# mgmt.net
KiCad netlist of a schematic drawn in Altium Designer
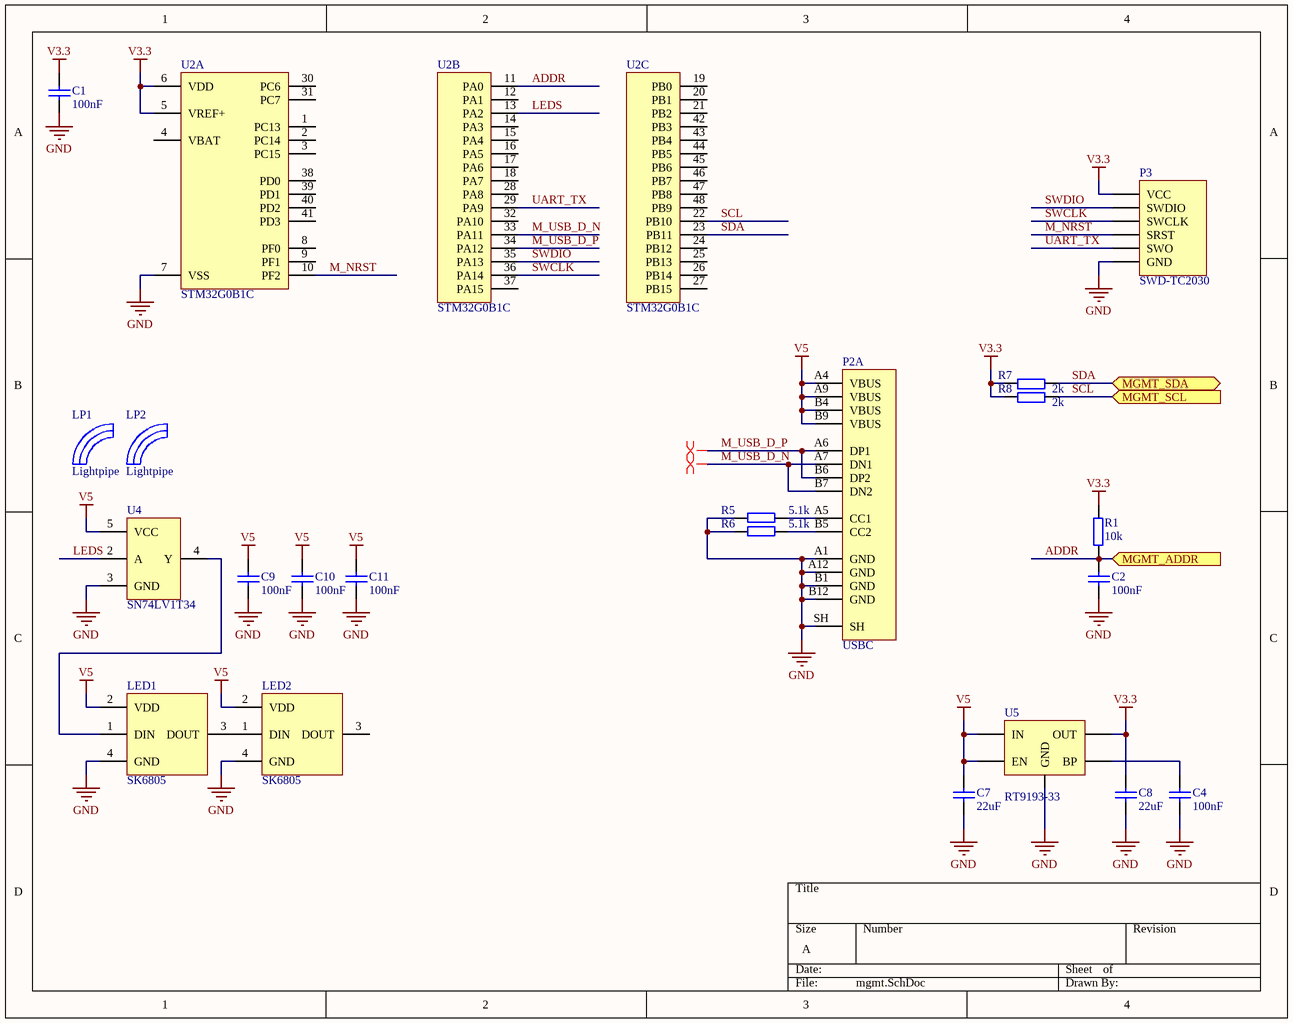
[diagram p0: mgmt.SchDoc]

(export (version "E")
  (design (tool "Eeschema 10.0.6"))
  (components
    (comp (ref "C1") (value "100nF") (footprint "0402") (libsource (lib "misc") (part "Capacitor")))
    (comp (ref "C2") (value "100nF") (footprint "0402") (libsource (lib "misc") (part "Capacitor")))
    (comp (ref "C4") (value "100nF") (footprint "0402") (libsource (lib "misc") (part "Capacitor")))
    (comp (ref "C7") (value "22uF") (footprint "0805") (libsource (lib "misc") (part "Capacitor")))
    (comp (ref "C8") (value "22uF") (footprint "0805") (libsource (lib "misc") (part "Capacitor")))
    (comp (ref "C9") (value "100nF") (footprint "0402") (libsource (lib "misc") (part "Capacitor")))
    (comp (ref "C10") (value "100nF") (footprint "0402") (libsource (lib "misc") (part "Capacitor")))
    (comp (ref "C11") (value "100nF") (footprint "0402") (libsource (lib "misc") (part "Capacitor")))
    (comp (ref "LED1") (value "SK6805") (footprint "EC15") (libsource (lib "misc") (part "SK6805")))
    (comp (ref "LED2") (value "SK6805") (footprint "EC15") (libsource (lib "misc") (part "SK6805")))
    (comp (ref "LP1")
      (value "Lightpipe")
      (footprint "SLP3-150-100-F")
      (libsource (lib "misc") (part "Lightpipe"))
    )
    (comp (ref "LP2")
      (value "Lightpipe")
      (footprint "SLP3-150-100-F")
      (libsource (lib "misc") (part "Lightpipe"))
    )
    (comp (ref "P2") (value "USBC") (footprint "U262-161N-4BVC11") (libsource (lib "misc") (part "USBC")))
    (comp (ref "P3")
      (value "SWD-TC2030")
      (footprint "TC2030-NL")
      (libsource (lib "misc") (part "SWD-TC2030"))
    )
    (comp (ref "R1") (value "10k") (footprint "0402") (libsource (lib "misc") (part "Resistor")))
    (comp (ref "R5") (value "5.1k") (footprint "0402") (libsource (lib "misc") (part "Resistor")))
    (comp (ref "R6") (value "5.1k") (footprint "0402") (libsource (lib "misc") (part "Resistor")))
    (comp (ref "R7") (value "2k") (footprint "0402") (libsource (lib "misc") (part "Resistor")))
    (comp (ref "R8") (value "2k") (footprint "0402") (libsource (lib "misc") (part "Resistor")))
    (comp (ref "U2") (value "STM32G0B1C") (footprint "QFP48") (libsource (lib "misc") (part "STM32G0B1C")))
    (comp (ref "U4")
      (value "SN74LV1T34")
      (footprint "SOT23-5")
      (description "Single Power Supply Single Buffer GATE CMOS Logic Level Shifter")
      (libsource (lib "misc") (part "SN74LV1T34"))
    )
    (comp (ref "U5") (value "RT9193-33") (footprint "SOT23-5") (libsource (lib "misc") (part "VREG_EN_BP")))
  )
  (nets
    (net (code "1") (name "/ADDR") (class "Default")
      (node (ref "C2") (pin "2") (pinfunction "2_2") (pintype "passive"))
      (node (ref "R1") (pin "1") (pinfunction "1_1") (pintype "passive"))
      (node (ref "U2") (pin "11") (pinfunction "PA0_11") (pintype "passive"))
    )
    (net (code "2") (name "/LEDS") (class "Default")
      (node (ref "U2") (pin "13") (pinfunction "PA2_13") (pintype "passive"))
      (node (ref "U4") (pin "2") (pinfunction "A_2") (pintype "passive"))
    )
    (net (code "3") (name "/M_NRST") (class "Default")
      (node (ref "P3") (pin "SRST") (pinfunction "SRST_SRST") (pintype "passive"))
      (node (ref "U2") (pin "10") (pinfunction "PF2_10") (pintype "passive"))
    )
    (net (code "4") (name "/M_USB_D_N") (class "Default")
      (node (ref "P2") (pin "A7") (pinfunction "DN1_A7") (pintype "passive"))
      (node (ref "P2") (pin "B7") (pinfunction "DN2_B7") (pintype "passive"))
      (node (ref "U2") (pin "33") (pinfunction "PA11_33") (pintype "passive"))
    )
    (net (code "5") (name "/M_USB_D_P") (class "Default")
      (node (ref "P2") (pin "A6") (pinfunction "DP1_A6") (pintype "passive"))
      (node (ref "P2") (pin "B6") (pinfunction "DP2_B6") (pintype "passive"))
      (node (ref "U2") (pin "34") (pinfunction "PA12_34") (pintype "passive"))
    )
    (net (code "6") (name "/SCL") (class "Default")
      (node (ref "R8") (pin "1") (pinfunction "1_1") (pintype "passive"))
      (node (ref "U2") (pin "22") (pinfunction "PB10_22") (pintype "passive"))
    )
    (net (code "7") (name "/SDA") (class "Default")
      (node (ref "R7") (pin "1") (pinfunction "1_1") (pintype "passive"))
      (node (ref "U2") (pin "23") (pinfunction "PB11_23") (pintype "passive"))
    )
    (net (code "8") (name "/SWCLK") (class "Default")
      (node (ref "P3") (pin "SWCLK") (pinfunction "SWCLK_SWCLK") (pintype "passive"))
      (node (ref "U2") (pin "36") (pinfunction "PA14_36") (pintype "passive"))
    )
    (net (code "9") (name "/SWDIO") (class "Default")
      (node (ref "P3") (pin "SWDIO") (pinfunction "SWDIO_SWDIO") (pintype "passive"))
      (node (ref "U2") (pin "35") (pinfunction "PA13_35") (pintype "passive"))
    )
    (net (code "10") (name "/UART_TX") (class "Default")
      (node (ref "P3") (pin "SWO") (pinfunction "SWO_SWO") (pintype "passive"))
      (node (ref "U2") (pin "29") (pinfunction "PA9_29") (pintype "passive"))
    )
    (net (code "11") (name "GND") (class "Default")
      (node (ref "C1") (pin "1") (pinfunction "1_1") (pintype "passive"))
      (node (ref "C10") (pin "1") (pinfunction "1_1") (pintype "passive"))
      (node (ref "C11") (pin "1") (pinfunction "1_1") (pintype "passive"))
      (node (ref "C2") (pin "1") (pinfunction "1_1") (pintype "passive"))
      (node (ref "C4") (pin "1") (pinfunction "1_1") (pintype "passive"))
      (node (ref "C7") (pin "1") (pinfunction "1_1") (pintype "passive"))
      (node (ref "C8") (pin "1") (pinfunction "1_1") (pintype "passive"))
      (node (ref "C9") (pin "1") (pinfunction "1_1") (pintype "passive"))
      (node (ref "LED1") (pin "4") (pinfunction "GND_4") (pintype "passive"))
      (node (ref "LED2") (pin "4") (pinfunction "GND_4") (pintype "passive"))
      (node (ref "P2") (pin "A1") (pinfunction "GND_A1") (pintype "passive"))
      (node (ref "P2") (pin "A12") (pinfunction "GND_A12") (pintype "passive"))
      (node (ref "P2") (pin "B1") (pinfunction "GND_B1") (pintype "passive"))
      (node (ref "P2") (pin "B12") (pinfunction "GND_B12") (pintype "passive"))
      (node (ref "P2") (pin "SH") (pinfunction "SH_SH") (pintype "passive"))
      (node (ref "P3") (pin "GND") (pinfunction "GND_GND") (pintype "passive"))
      (node (ref "R5") (pin "1") (pinfunction "1_1") (pintype "passive"))
      (node (ref "R6") (pin "1") (pinfunction "1_1") (pintype "passive"))
      (node (ref "U2") (pin "7") (pinfunction "VSS_7") (pintype "passive"))
      (node (ref "U4") (pin "3") (pinfunction "GND_3") (pintype "passive"))
      (node (ref "U5") (pin "GND") (pinfunction "GND_GND") (pintype "passive"))
    )
    (net (code "12") (name "Net-(C4-Pad2)") (class "Default")
      (node (ref "C4") (pin "2") (pinfunction "2_2") (pintype "passive"))
      (node (ref "U5") (pin "BP") (pinfunction "BP_BP") (pintype "passive"))
    )
    (net (code "13") (name "Net-(LED1-DIN)") (class "Default")
      (node (ref "LED1") (pin "1") (pinfunction "DIN_1") (pintype "passive"))
      (node (ref "U4") (pin "4") (pinfunction "Y_4") (pintype "passive"))
    )
    (net (code "14") (name "Net-(LED1-DOUT)") (class "Default")
      (node (ref "LED1") (pin "3") (pinfunction "DOUT_3") (pintype "passive"))
      (node (ref "LED2") (pin "1") (pinfunction "DIN_1") (pintype "passive"))
    )
    (net (code "15") (name "Net-(P2A-CC1)") (class "Default")
      (node (ref "P2") (pin "A5") (pinfunction "CC1_A5") (pintype "passive"))
      (node (ref "R5") (pin "2") (pinfunction "2_2") (pintype "passive"))
    )
    (net (code "16") (name "Net-(P2A-CC2)") (class "Default")
      (node (ref "P2") (pin "B5") (pinfunction "CC2_B5") (pintype "passive"))
      (node (ref "R6") (pin "2") (pinfunction "2_2") (pintype "passive"))
    )
    (net (code "17") (name "V3.3") (class "Default")
      (node (ref "C1") (pin "2") (pinfunction "2_2") (pintype "passive"))
      (node (ref "C8") (pin "2") (pinfunction "2_2") (pintype "passive"))
      (node (ref "P3") (pin "VCC") (pinfunction "VCC_VCC") (pintype "passive"))
      (node (ref "R1") (pin "2") (pinfunction "2_2") (pintype "passive"))
      (node (ref "R7") (pin "2") (pinfunction "2_2") (pintype "passive"))
      (node (ref "R8") (pin "2") (pinfunction "2_2") (pintype "passive"))
      (node (ref "U2") (pin "5") (pinfunction "VREF+_5") (pintype "passive"))
      (node (ref "U2") (pin "6") (pinfunction "VDD_6") (pintype "passive"))
      (node (ref "U5") (pin "OUT") (pinfunction "OUT_OUT") (pintype "passive"))
    )
    (net (code "18") (name "V5") (class "Default")
      (node (ref "C10") (pin "2") (pinfunction "2_2") (pintype "passive"))
      (node (ref "C11") (pin "2") (pinfunction "2_2") (pintype "passive"))
      (node (ref "C7") (pin "2") (pinfunction "2_2") (pintype "passive"))
      (node (ref "C9") (pin "2") (pinfunction "2_2") (pintype "passive"))
      (node (ref "LED1") (pin "2") (pinfunction "VDD_2") (pintype "passive"))
      (node (ref "LED2") (pin "2") (pinfunction "VDD_2") (pintype "passive"))
      (node (ref "P2") (pin "A4") (pinfunction "VBUS_A4") (pintype "passive"))
      (node (ref "P2") (pin "A9") (pinfunction "VBUS_A9") (pintype "passive"))
      (node (ref "P2") (pin "B4") (pinfunction "VBUS_B4") (pintype "passive"))
      (node (ref "P2") (pin "B9") (pinfunction "VBUS_B9") (pintype "passive"))
      (node (ref "U4") (pin "5") (pinfunction "VCC_5") (pintype "passive"))
      (node (ref "U5") (pin "EN") (pinfunction "EN_EN") (pintype "passive"))
      (node (ref "U5") (pin "IN") (pinfunction "IN_IN") (pintype "passive"))
    )
    (net (code "19") (name "unconnected-(LED2-DOUT-Pad3)") (class "Default")
      (node (ref "LED2") (pin "3") (pinfunction "DOUT_3") (pintype "passive"))
    )
    (net (code "20") (name "unconnected-(U2A-PC6-Pad30)") (class "Default")
      (node (ref "U2") (pin "30") (pinfunction "PC6_30") (pintype "passive"))
    )
    (net (code "21") (name "unconnected-(U2A-PC7-Pad31)") (class "Default")
      (node (ref "U2") (pin "31") (pinfunction "PC7_31") (pintype "passive"))
    )
    (net (code "22") (name "unconnected-(U2A-PC13-Pad1)") (class "Default")
      (node (ref "U2") (pin "1") (pinfunction "PC13_1") (pintype "passive"))
    )
    (net (code "23") (name "unconnected-(U2A-PC14-Pad2)") (class "Default")
      (node (ref "U2") (pin "2") (pinfunction "PC14_2") (pintype "passive"))
    )
    (net (code "24") (name "unconnected-(U2A-PC15-Pad3)") (class "Default")
      (node (ref "U2") (pin "3") (pinfunction "PC15_3") (pintype "passive"))
    )
    (net (code "25") (name "unconnected-(U2A-PD0-Pad38)") (class "Default")
      (node (ref "U2") (pin "38") (pinfunction "PD0_38") (pintype "passive"))
    )
    (net (code "26") (name "unconnected-(U2A-PD1-Pad39)") (class "Default")
      (node (ref "U2") (pin "39") (pinfunction "PD1_39") (pintype "passive"))
    )
    (net (code "27") (name "unconnected-(U2A-PD2-Pad40)") (class "Default")
      (node (ref "U2") (pin "40") (pinfunction "PD2_40") (pintype "passive"))
    )
    (net (code "28") (name "unconnected-(U2A-PD3-Pad41)") (class "Default")
      (node (ref "U2") (pin "41") (pinfunction "PD3_41") (pintype "passive"))
    )
    (net (code "29") (name "unconnected-(U2A-PF0-Pad8)") (class "Default")
      (node (ref "U2") (pin "8") (pinfunction "PF0_8") (pintype "passive"))
    )
    (net (code "30") (name "unconnected-(U2A-PF1-Pad9)") (class "Default")
      (node (ref "U2") (pin "9") (pinfunction "PF1_9") (pintype "passive"))
    )
    (net (code "31") (name "unconnected-(U2A-VBAT-Pad4)") (class "Default")
      (node (ref "U2") (pin "4") (pinfunction "VBAT_4") (pintype "passive"))
    )
    (net (code "32") (name "unconnected-(U2B-PA1-Pad12)") (class "Default")
      (node (ref "U2") (pin "12") (pinfunction "PA1_12") (pintype "passive"))
    )
    (net (code "33") (name "unconnected-(U2B-PA3-Pad14)") (class "Default")
      (node (ref "U2") (pin "14") (pinfunction "PA3_14") (pintype "passive"))
    )
    (net (code "34") (name "unconnected-(U2B-PA4-Pad15)") (class "Default")
      (node (ref "U2") (pin "15") (pinfunction "PA4_15") (pintype "passive"))
    )
    (net (code "35") (name "unconnected-(U2B-PA5-Pad16)") (class "Default")
      (node (ref "U2") (pin "16") (pinfunction "PA5_16") (pintype "passive"))
    )
    (net (code "36") (name "unconnected-(U2B-PA6-Pad17)") (class "Default")
      (node (ref "U2") (pin "17") (pinfunction "PA6_17") (pintype "passive"))
    )
    (net (code "37") (name "unconnected-(U2B-PA7-Pad18)") (class "Default")
      (node (ref "U2") (pin "18") (pinfunction "PA7_18") (pintype "passive"))
    )
    (net (code "38") (name "unconnected-(U2B-PA8-Pad28)") (class "Default")
      (node (ref "U2") (pin "28") (pinfunction "PA8_28") (pintype "passive"))
    )
    (net (code "39") (name "unconnected-(U2B-PA10-Pad32)") (class "Default")
      (node (ref "U2") (pin "32") (pinfunction "PA10_32") (pintype "passive"))
    )
    (net (code "40") (name "unconnected-(U2B-PA15-Pad37)") (class "Default")
      (node (ref "U2") (pin "37") (pinfunction "PA15_37") (pintype "passive"))
    )
    (net (code "41") (name "unconnected-(U2C-PB0-Pad19)") (class "Default")
      (node (ref "U2") (pin "19") (pinfunction "PB0_19") (pintype "passive"))
    )
    (net (code "42") (name "unconnected-(U2C-PB1-Pad20)") (class "Default")
      (node (ref "U2") (pin "20") (pinfunction "PB1_20") (pintype "passive"))
    )
    (net (code "43") (name "unconnected-(U2C-PB2-Pad21)") (class "Default")
      (node (ref "U2") (pin "21") (pinfunction "PB2_21") (pintype "passive"))
    )
    (net (code "44") (name "unconnected-(U2C-PB3-Pad42)") (class "Default")
      (node (ref "U2") (pin "42") (pinfunction "PB3_42") (pintype "passive"))
    )
    (net (code "45") (name "unconnected-(U2C-PB4-Pad43)") (class "Default")
      (node (ref "U2") (pin "43") (pinfunction "PB4_43") (pintype "passive"))
    )
    (net (code "46") (name "unconnected-(U2C-PB5-Pad44)") (class "Default")
      (node (ref "U2") (pin "44") (pinfunction "PB5_44") (pintype "passive"))
    )
    (net (code "47") (name "unconnected-(U2C-PB6-Pad45)") (class "Default")
      (node (ref "U2") (pin "45") (pinfunction "PB6_45") (pintype "passive"))
    )
    (net (code "48") (name "unconnected-(U2C-PB7-Pad46)") (class "Default")
      (node (ref "U2") (pin "46") (pinfunction "PB7_46") (pintype "passive"))
    )
    (net (code "49") (name "unconnected-(U2C-PB8-Pad47)") (class "Default")
      (node (ref "U2") (pin "47") (pinfunction "PB8_47") (pintype "passive"))
    )
    (net (code "50") (name "unconnected-(U2C-PB9-Pad48)") (class "Default")
      (node (ref "U2") (pin "48") (pinfunction "PB9_48") (pintype "passive"))
    )
    (net (code "51") (name "unconnected-(U2C-PB12-Pad24)") (class "Default")
      (node (ref "U2") (pin "24") (pinfunction "PB12_24") (pintype "passive"))
    )
    (net (code "52") (name "unconnected-(U2C-PB13-Pad25)") (class "Default")
      (node (ref "U2") (pin "25") (pinfunction "PB13_25") (pintype "passive"))
    )
    (net (code "53") (name "unconnected-(U2C-PB14-Pad26)") (class "Default")
      (node (ref "U2") (pin "26") (pinfunction "PB14_26") (pintype "passive"))
    )
    (net (code "54") (name "unconnected-(U2C-PB15-Pad27)") (class "Default")
      (node (ref "U2") (pin "27") (pinfunction "PB15_27") (pintype "passive"))
    )
  )
)
